# Amplifier.net
KiCad netlist of a schematic drawn in Altium Designer
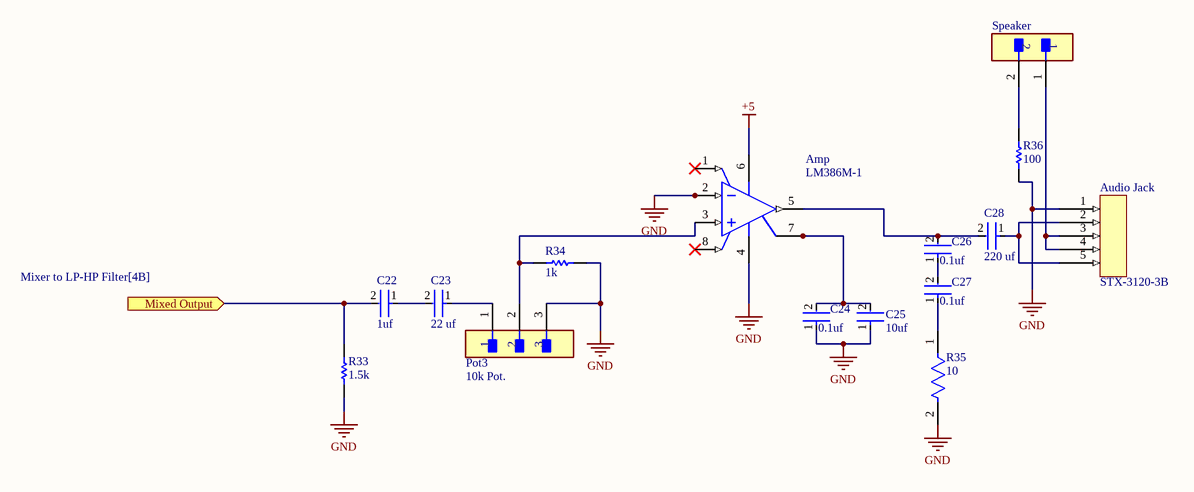
[diagram p0: Amplifier.SchDoc]

(export (version "E")
  (design (tool "Eeschema 10.0.6"))
  (components
    (comp (ref "Amp")
      (value "LM386M-1")
      (footprint "TI-D8_M")
      (description "Low Voltage Audio Power Amplifier, 0 to 70 degC, 8-pin SOIC (D8), Green (RoHS & no Sb/Br)")
      (fields (field (name "PARTNUMBER") "LM386M-1/NOPB") (field (name "MANUFACTURER") "Texas Instruments"))
      (libsource (lib "Altium Content Vault") (part "TI-LM386undefined"))
    )
    (comp (ref "Audio Jack")
      (value "STX-3120-3B")
      (footprint "STX3100")
      (description "3 Pole(s), Female, Solder Terminal, Locking, Jack")
      (libsource (lib "Ryamgordon") (part "STX-3120-3B"))
    )
    (comp (ref "C22")
      (value "1uf")
      (footprint "FP-K105Z20Y5VF5TL2-MFG")
      (description "CAP CER 1UF 50V Y5V RADIAL")
      (fields
        (field (name "TOLERANCE") "-20+80%")
        (field (name "OCTOPART") "https://octopart.com/k105z20y5vf5tl2-vishay-39475252")
      )
      (libsource (lib "Altium Content Vault") (part "11868f565c42a9108669ba33697ecf6"))
    )
    (comp (ref "C23")
      (value "22 uf")
      (footprint "FP-RCEWM1-MFG")
      (description "CAP CER 22UF 25V X7R RADIAL")
      (fields (field (name "TOLERANCE") "20%"))
      (libsource (lib "Altium Content Vault") (part "02cd4be3c70576c341d710602a673aa"))
    )
    (comp (ref "C24")
      (value "0.1uf")
      (footprint "FP-SR20-MFG")
      (description "CAP CER 0.1UF 50V X7R RADIAL")
      (fields (field (name "VOLTAGE") "50V") (field (name "TOLERANCE") "10%"))
      (libsource (lib "Altium Content Vault") (part "11868f565c42a9108669ba33697ecf6"))
    )
    (comp (ref "C25")
      (value "10uf")
      (footprint "FP-RCE3DB-MFG")
      (description "Cap Ceramic 10uF 25V X7R ±10% Radial 2.5mm +125°C Automotive Ammo Pack")
      (fields (field (name "TOLERANCE") "10%"))
      (libsource (lib "Altium Content Vault") (part "b4654b650e69147ec39a6b967a45e02"))
    )
    (comp (ref "C26")
      (value "0.1uf")
      (footprint "FP-SR20-MFG")
      (description "CAP CER 0.1UF 50V X7R RADIAL")
      (fields (field (name "VOLTAGE") "50V") (field (name "TOLERANCE") "10%"))
      (libsource (lib "Altium Content Vault") (part "11868f565c42a9108669ba33697ecf6"))
    )
    (comp (ref "C27")
      (value "0.1uf")
      (footprint "FP-SR20-MFG")
      (description "CAP CER 0.1UF 50V X7R RADIAL")
      (fields (field (name "VOLTAGE") "50V") (field (name "TOLERANCE") "10%"))
      (libsource (lib "Altium Content Vault") (part "11868f565c42a9108669ba33697ecf6"))
    )
    (comp (ref "C28")
      (value "220 uf")
      (footprint "FP-RCEWM1-MFG")
      (description "CAP CER 22UF 25V X7R RADIAL")
      (fields (field (name "TOLERANCE") "20%"))
      (libsource (lib "Altium Content Vault") (part "02cd4be3c70576c341d710602a673aa"))
    )
    (comp (ref "Pot3")
      (value "10k Pot.")
      (footprint "FP-90120-0123-MFG")
      (description "CONN HEADER VERT 3POS 2.54MM")
      (libsource (lib "Altium Content Vault") (part "0d3f023dd272f625e17a2be33dea85f"))
    )
    (comp (ref "R33")
      (value "1.5k")
      (footprint "RESC2013X60X40LL20T25")
      (fields (field (name "MANUFACTURER") "Panasonic") (field (name "PART NUMBER") "ERA6AEB152V"))
      (libsource (lib "Altium Content Vault") (part "RES"))
    )
    (comp (ref "R34")
      (value "1k")
      (footprint "RESC2013X70X40ML20T20")
      (description "Chip Resistor, 1 KOhm, +/- 1%, 0.125 W, -55 to 155 degC, 0805 (2012 Metric), RoHS, Tape and Reel")
      (fields (field (name "MANUFACTURER") "Panasonic"))
      (libsource (lib "Altium Content Vault") (part "RES-2"))
    )
    (comp (ref "R35")
      (value "10")
      (footprint "FP-RN732A-MFG")
      (description "SMD Chip Resistor, Thin Film, 10Ω, 100 V, 0805 [2012 Metric], 100 mW, 0.1%, RN73 Series")
      (fields
        (field (name "MANUFACTURER") "TE Connectivity")
        (field (name "MANUFACTURER PART NUMBER") "RN73C2A10RBTG")
      )
      (libsource (lib "Altium Content Vault") (part "1029c3af85768c4190bb7ad29bc67b5"))
    )
    (comp (ref "R36")
      (value "100")
      (footprint "RESC2013X60X40ML20T25")
      (fields (field (name "MANUFACTURER") "Panasonic") (field (name "PART NUMBER") "ERA6AEB101V"))
      (libsource (lib "Altium Content Vault") (part "RES"))
    )
    (comp (ref "Speaker")
      (value "M20-9990246")
      (footprint "FP-M20-9990246-MFG")
      (description "CONN HEADER VERT 2POS 2.54MM")
      (fields
        (field (name "OCTOPART") "https://octopart.com/m20-9990246-harwin-2590635")
        (field (name "MANUFACTURER") "Harwin")
      )
      (libsource (lib "Altium Content Vault") (part "3bc925449376181038e59eaffc5286c"))
    )
  )
  (nets
    (net (code "1") (name "+5") (class "Default")
      (node (ref "Amp") (pin "6") (pinfunction "VS_6") (pintype "power_in"))
    )
    (net (code "2") (name "/Mixed Output") (class "Default")
      (node (ref "C22") (pin "2") (pinfunction "2_2") (pintype "passive"))
      (node (ref "R33") (pin "2") (pinfunction "2_2") (pintype "passive"))
    )
    (net (code "3") (name "GND") (class "Default")
      (node (ref "Amp") (pin "2") (pinfunction "IN-_2") (pintype "input"))
      (node (ref "Amp") (pin "4") (pinfunction "GND_4") (pintype "power_in"))
      (node (ref "Audio Jack") (pin "1") (pintype "input"))
      (node (ref "C24") (pin "1") (pinfunction "1_1") (pintype "passive"))
      (node (ref "C25") (pin "1") (pinfunction "1_1") (pintype "passive"))
      (node (ref "Pot3") (pin "3") (pinfunction "3_3") (pintype "passive"))
      (node (ref "R33") (pin "1") (pinfunction "1_1") (pintype "passive"))
      (node (ref "R34") (pin "2") (pinfunction "2_2") (pintype "passive"))
      (node (ref "R35") (pin "2") (pinfunction "2_2") (pintype "passive"))
      (node (ref "R36") (pin "1") (pinfunction "1_1") (pintype "passive"))
    )
    (net (code "4") (name "Net-(Amp-BYPASS)") (class "Default")
      (node (ref "Amp") (pin "7") (pinfunction "BYPASS_7") (pintype "passive"))
      (node (ref "C24") (pin "2") (pinfunction "2_2") (pintype "passive"))
      (node (ref "C25") (pin "2") (pinfunction "2_2") (pintype "passive"))
    )
    (net (code "5") (name "Net-(Amp-IN+)") (class "Default")
      (node (ref "Amp") (pin "3") (pinfunction "IN+_3") (pintype "input"))
      (node (ref "Pot3") (pin "2") (pinfunction "2_2") (pintype "passive"))
      (node (ref "R34") (pin "1") (pinfunction "1_1") (pintype "passive"))
    )
    (net (code "6") (name "Net-(Amp-VOUT)") (class "Default")
      (node (ref "Amp") (pin "5") (pinfunction "VOUT_5") (pintype "output"))
      (node (ref "C26") (pin "2") (pinfunction "2_2") (pintype "passive"))
      (node (ref "C28") (pin "2") (pinfunction "2_2") (pintype "passive"))
    )
    (net (code "7") (name "Net-(Audio Jack-Pad2)") (class "Default")
      (node (ref "Audio Jack") (pin "2") (pintype "input"))
      (node (ref "Audio Jack") (pin "5") (pintype "input"))
      (node (ref "C28") (pin "1") (pinfunction "1_1") (pintype "passive"))
    )
    (net (code "8") (name "Net-(Audio Jack-Pad3)") (class "Default")
      (node (ref "Audio Jack") (pin "3") (pintype "input"))
      (node (ref "Audio Jack") (pin "4") (pintype "input"))
      (node (ref "Speaker") (pin "1") (pinfunction "1_1") (pintype "passive"))
    )
    (net (code "9") (name "Net-(C22-Pad1)") (class "Default")
      (node (ref "C22") (pin "1") (pinfunction "1_1") (pintype "passive"))
      (node (ref "C23") (pin "2") (pinfunction "2_2") (pintype "passive"))
    )
    (net (code "10") (name "Net-(C23-Pad1)") (class "Default")
      (node (ref "C23") (pin "1") (pinfunction "1_1") (pintype "passive"))
      (node (ref "Pot3") (pin "1") (pinfunction "1_1") (pintype "passive"))
    )
    (net (code "11") (name "Net-(C26-Pad1)") (class "Default")
      (node (ref "C26") (pin "1") (pinfunction "1_1") (pintype "passive"))
      (node (ref "C27") (pin "2") (pinfunction "2_2") (pintype "passive"))
    )
    (net (code "12") (name "Net-(C27-Pad1)") (class "Default")
      (node (ref "C27") (pin "1") (pinfunction "1_1") (pintype "passive"))
      (node (ref "R35") (pin "1") (pinfunction "1_1") (pintype "passive"))
    )
    (net (code "13") (name "Net-(R36-Pad2)") (class "Default")
      (node (ref "R36") (pin "2") (pinfunction "2_2") (pintype "passive"))
      (node (ref "Speaker") (pin "2") (pinfunction "2_2") (pintype "passive"))
    )
    (net (code "14") (name "unconnected-(Amp-GAIN-Pad1)") (class "Default")
      (node (ref "Amp") (pin "1") (pinfunction "GAIN_1") (pintype "input+no_connect"))
    )
    (net (code "15") (name "unconnected-(Amp-GAIN-Pad8)") (class "Default")
      (node (ref "Amp") (pin "8") (pinfunction "GAIN_8") (pintype "input+no_connect"))
    )
  )
)
